# PROFIBUS_V4.net
KiCad netlist of a schematic drawn in EAGLE
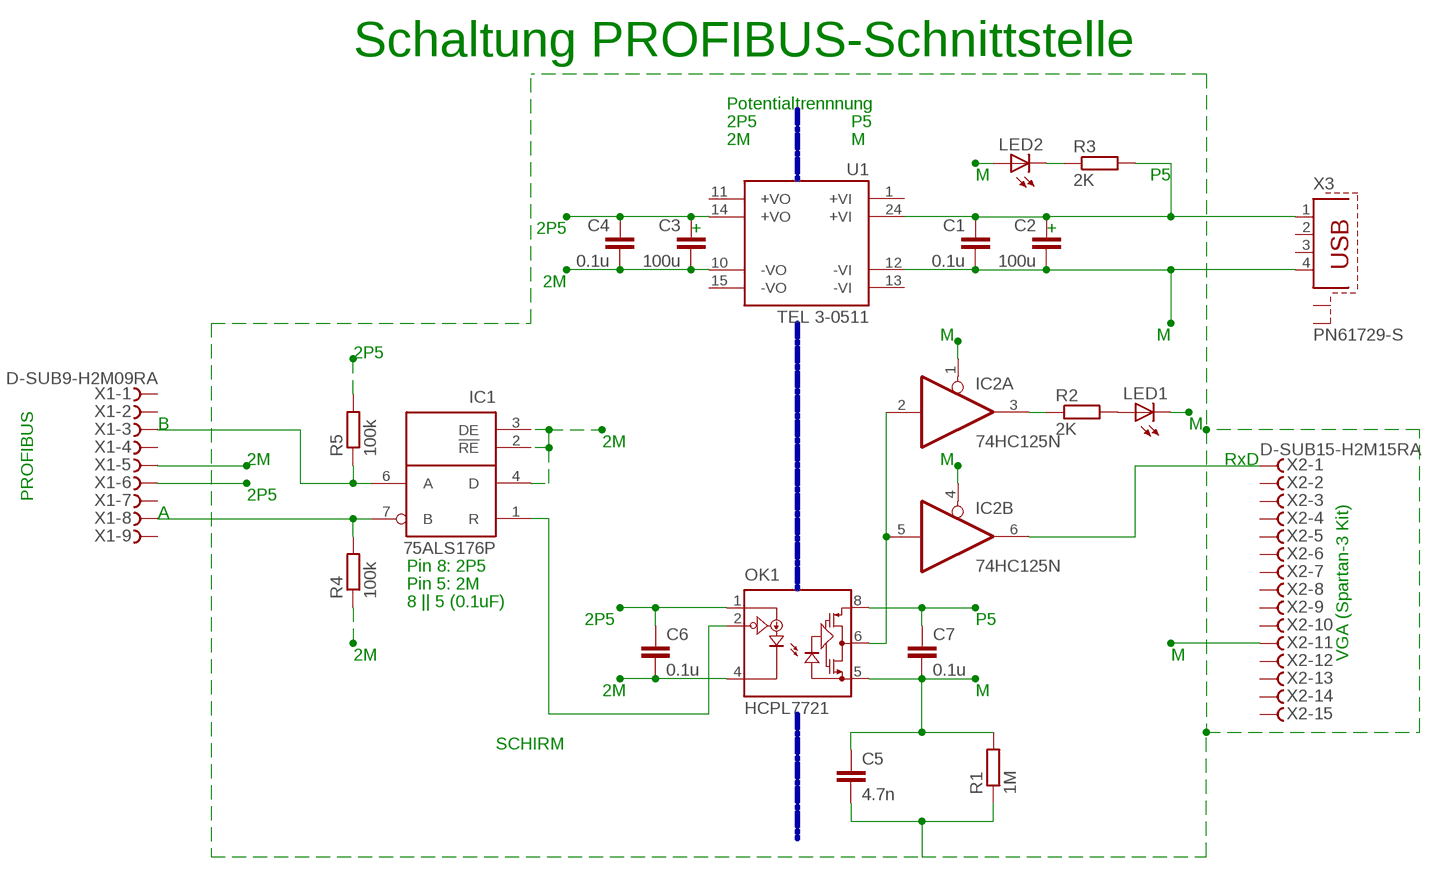
[diagram p0: schematic, sheet 1]

(export (version "E")
  (design (tool "Eeschema 10.0.6"))
  (components
    (comp (ref "C1")
      (value "0.1u")
      (footprint "eagle-import:C2.5-3")
      (libsource (lib "eagle-import") (part "C2,5-3"))
    )
    (comp (ref "C2")
      (value "100u")
      (footprint "eagle-import:C2.5-3")
      (libsource (lib "eagle-import") (part "C2,5-3"))
    )
    (comp (ref "C3")
      (value "100u")
      (footprint "eagle-import:C2.5-3")
      (libsource (lib "eagle-import") (part "C2,5-3"))
    )
    (comp (ref "C4")
      (value "0.1u")
      (footprint "eagle-import:C2.5-3")
      (libsource (lib "eagle-import") (part "C2,5-3"))
    )
    (comp (ref "C5")
      (value "4.7n")
      (footprint "eagle-import:C2.5-3")
      (libsource (lib "eagle-import") (part "C2,5-3"))
    )
    (comp (ref "C6")
      (value "0.1u")
      (footprint "eagle-import:C2.5-3")
      (libsource (lib "eagle-import") (part "C2,5-3"))
    )
    (comp (ref "C7")
      (value "0.1u")
      (footprint "eagle-import:C2.5-3")
      (libsource (lib "eagle-import") (part "C2,5-3"))
    )
    (comp (ref "IC1")
      (value "75ALS176P")
      (footprint "eagle-import:DIL08")
      (fields (field (name "MF") "TEXAS INSTRUMENTS") (field (name "MPN") "SN75ALS176P"))
      (libsource (lib "eagle-import") (part "75ALS176P"))
    )
    (comp (ref "IC2")
      (value "74HC125N")
      (footprint "eagle-import:DIL14")
      (libsource (lib "eagle-import") (part "74125NHC"))
    )
    (comp (ref "LED1")
      (value "TLLY4400")
      (footprint "eagle-import:LED3MM")
      (fields (field (name "MF") "VISHAY SEMICONDUCTOR"))
      (libsource (lib "eagle-import") (part "TLLY4400"))
    )
    (comp (ref "LED2")
      (value "TLLG4400")
      (footprint "eagle-import:LED3MM")
      (fields (field (name "MF") "VISHAY SEMICONDUCTOR"))
      (libsource (lib "eagle-import") (part "TLLG4400"))
    )
    (comp (ref "OK1")
      (value "HCPL7721")
      (footprint "eagle-import:DIL08")
      (fields (field (name "MF") "AGILENT TECHNOLOGIES") (field (name "MPN") "HCPL-7721"))
      (libsource (lib "eagle-import") (part "HCPL7721"))
    )
    (comp (ref "R1")
      (value "1M")
      (footprint "eagle-import:0204_7")
      (libsource (lib "eagle-import") (part "R-EU_0204/7"))
    )
    (comp (ref "R2")
      (value "2K")
      (footprint "eagle-import:0204_7")
      (libsource (lib "eagle-import") (part "R-EU_0204/7"))
    )
    (comp (ref "R3")
      (value "2K")
      (footprint "eagle-import:0204_7")
      (libsource (lib "eagle-import") (part "R-EU_0204/7"))
    )
    (comp (ref "R4")
      (value "100k")
      (footprint "eagle-import:0204_7")
      (libsource (lib "eagle-import") (part "R-EU_0204/7"))
    )
    (comp (ref "R5")
      (value "100k")
      (footprint "eagle-import:0204_7")
      (libsource (lib "eagle-import") (part "R-EU_0204/7"))
    )
    (comp (ref "U1")
      (value "TEL 3-0511")
      (footprint "eagle-import:AM3N_DIL24")
      (libsource (lib "eagle-import") (part "AM3N-S0505"))
    )
    (comp (ref "X1")
      (value "D-SUB9-H2M09RA")
      (footprint "eagle-import:H2M09RA")
      (libsource (lib "eagle-import") (part "D-SUB9-H2M09RA"))
    )
    (comp (ref "X2")
      (value "D-SUB15-H2M15RA")
      (footprint "eagle-import:H2M15RA")
      (fields (field (name "MPN") "H2M15RA29B"))
      (libsource (lib "eagle-import") (part "D-SUB15-H2M15RA"))
    )
    (comp (ref "X3")
      (value "PN61729-S")
      (footprint "eagle-import:PN61729-S")
      (libsource (lib "eagle-import") (part "PN61729-S"))
    )
  )
  (nets
    (net (code "1") (name "/+VI") (class "Default")
      (node (ref "U1") (pin "1") (pinfunction "+VI_1") (pintype "power_in"))
    )
    (net (code "2") (name "/+VO") (class "Default")
      (node (ref "U1") (pin "11") (pinfunction "+VO_11") (pintype "power_in"))
    )
    (net (code "3") (name "/-VI") (class "Default")
      (node (ref "U1") (pin "13") (pinfunction "-VI_13") (pintype "power_in"))
    )
    (net (code "4") (name "/-VO") (class "Default")
      (node (ref "U1") (pin "15") (pinfunction "-VO_15") (pintype "power_in"))
    )
    (net (code "5") (name "Net-(C1-Pad1)") (class "Default")
      (node (ref "C1") (pin "1") (pinfunction "1_1") (pintype "passive"))
      (node (ref "C2") (pin "1") (pinfunction "1_1") (pintype "passive"))
      (node (ref "R3") (pin "2") (pinfunction "2_2") (pintype "passive"))
      (node (ref "U1") (pin "24") (pinfunction "+VI_24") (pintype "power_in"))
      (node (ref "X3") (pin "1") (pinfunction "1_1") (pintype "passive"))
    )
    (net (code "6") (name "Net-(C1-Pad2)") (class "Default")
      (node (ref "C1") (pin "2") (pinfunction "2_2") (pintype "passive"))
      (node (ref "C2") (pin "2") (pinfunction "2_2") (pintype "passive"))
      (node (ref "U1") (pin "12") (pinfunction "-VI_12") (pintype "power_in"))
      (node (ref "X3") (pin "4") (pinfunction "4_4") (pintype "passive"))
    )
    (net (code "7") (name "Net-(C3-Pad1)") (class "Default")
      (node (ref "C3") (pin "1") (pinfunction "1_1") (pintype "passive"))
      (node (ref "C4") (pin "1") (pinfunction "1_1") (pintype "passive"))
      (node (ref "U1") (pin "14") (pinfunction "+VO_14") (pintype "power_in"))
    )
    (net (code "8") (name "Net-(C3-Pad2)") (class "Default")
      (node (ref "C3") (pin "2") (pinfunction "2_2") (pintype "passive"))
      (node (ref "C4") (pin "2") (pinfunction "2_2") (pintype "passive"))
      (node (ref "U1") (pin "10") (pinfunction "-VO_10") (pintype "power_in"))
    )
    (net (code "9") (name "Net-(C5-Pad2)") (class "Default")
      (node (ref "C5") (pin "2") (pinfunction "2_2") (pintype "passive"))
      (node (ref "R1") (pin "1") (pinfunction "1_1") (pintype "passive"))
    )
    (net (code "10") (name "Net-(IC1A-A)") (class "Default")
      (node (ref "IC1") (pin "6") (pinfunction "A_6") (pintype "bidirectional"))
      (node (ref "R5") (pin "1") (pinfunction "1_1") (pintype "passive"))
      (node (ref "X1") (pin "3") (pinfunction "F_3") (pintype "passive"))
    )
    (net (code "11") (name "Net-(IC1A-B)") (class "Default")
      (node (ref "IC1") (pin "7") (pinfunction "B_7") (pintype "bidirectional"))
      (node (ref "R4") (pin "2") (pinfunction "2_2") (pintype "passive"))
      (node (ref "X1") (pin "8") (pinfunction "F_8") (pintype "passive"))
    )
    (net (code "12") (name "Net-(IC1A-D)") (class "Default")
      (node (ref "IC1") (pin "2") (pinfunction "~{RE}_2") (pintype "input"))
      (node (ref "IC1") (pin "3") (pinfunction "DE_3") (pintype "input"))
      (node (ref "IC1") (pin "4") (pinfunction "D_4") (pintype "input"))
    )
    (net (code "13") (name "Net-(IC1A-R)") (class "Default")
      (node (ref "IC1") (pin "1") (pinfunction "R_1") (pintype "output"))
      (node (ref "OK1") (pin "2") (pinfunction "VI_2") (pintype "input"))
    )
    (net (code "14") (name "Net-(IC2A-I)") (class "Default")
      (node (ref "IC2") (pin "2") (pinfunction "I_2") (pintype "input"))
      (node (ref "IC2") (pin "5") (pinfunction "I_5") (pintype "input"))
      (node (ref "OK1") (pin "6") (pinfunction "VO_6") (pintype "passive"))
    )
    (net (code "15") (name "Net-(IC2A-O)") (class "Default")
      (node (ref "IC2") (pin "3") (pinfunction "O_3") (pintype "tri_state"))
      (node (ref "R2") (pin "1") (pinfunction "1_1") (pintype "passive"))
    )
    (net (code "16") (name "Net-(IC2B-O)") (class "Default")
      (node (ref "IC2") (pin "6") (pinfunction "O_6") (pintype "tri_state"))
      (node (ref "X2") (pin "1") (pinfunction "F_1") (pintype "passive"))
    )
    (net (code "17") (name "Net-(LED1-PadA)") (class "Default")
      (node (ref "LED1") (pin "A") (pinfunction "A_A") (pintype "passive"))
      (node (ref "R2") (pin "2") (pinfunction "2_2") (pintype "passive"))
    )
    (net (code "18") (name "Net-(LED2-C)") (class "Default")
      (node (ref "LED2") (pin "K") (pinfunction "C_K") (pintype "passive"))
      (node (ref "R3") (pin "1") (pinfunction "1_1") (pintype "passive"))
    )
    (net (code "19") (name "Net-(OK1-GND1)") (class "Default")
      (node (ref "C6") (pin "2") (pinfunction "2_2") (pintype "passive"))
      (node (ref "OK1") (pin "4") (pinfunction "GND1_4") (pintype "passive"))
    )
    (net (code "20") (name "Net-(OK1-GND2)") (class "Default")
      (node (ref "C5") (pin "1") (pinfunction "1_1") (pintype "passive"))
      (node (ref "C7") (pin "2") (pinfunction "2_2") (pintype "passive"))
      (node (ref "OK1") (pin "5") (pinfunction "GND2_5") (pintype "passive"))
      (node (ref "R1") (pin "2") (pinfunction "2_2") (pintype "passive"))
    )
    (net (code "21") (name "Net-(OK1-VDD1)") (class "Default")
      (node (ref "C6") (pin "1") (pinfunction "1_1") (pintype "passive"))
      (node (ref "OK1") (pin "1") (pinfunction "VDD1_1") (pintype "passive"))
    )
    (net (code "22") (name "Net-(OK1-VDD2)") (class "Default")
      (node (ref "C7") (pin "1") (pinfunction "1_1") (pintype "passive"))
      (node (ref "OK1") (pin "8") (pinfunction "VDD2_8") (pintype "passive"))
    )
    (net (code "23") (name "unconnected-(IC2A-OE-Pad1)") (class "Default")
      (node (ref "IC2") (pin "1") (pinfunction "OE_1") (pintype "input"))
    )
    (net (code "24") (name "unconnected-(IC2B-OE-Pad4)") (class "Default")
      (node (ref "IC2") (pin "4") (pinfunction "OE_4") (pintype "input"))
    )
    (net (code "25") (name "unconnected-(LED1-C-PadK)") (class "Default")
      (node (ref "LED1") (pin "K") (pinfunction "C_K") (pintype "passive"))
    )
    (net (code "26") (name "unconnected-(LED2-PadA)") (class "Default")
      (node (ref "LED2") (pin "A") (pinfunction "A_A") (pintype "passive"))
    )
    (net (code "27") (name "unconnected-(R4-Pad1)") (class "Default")
      (node (ref "R4") (pin "1") (pinfunction "1_1") (pintype "passive"))
    )
    (net (code "28") (name "unconnected-(R5-Pad2)") (class "Default")
      (node (ref "R5") (pin "2") (pinfunction "2_2") (pintype "passive"))
    )
    (net (code "29") (name "unconnected-(X1A-F-Pad1)") (class "Default")
      (node (ref "X1") (pin "1") (pinfunction "F_1") (pintype "passive"))
    )
    (net (code "30") (name "unconnected-(X1B-F-Pad2)") (class "Default")
      (node (ref "X1") (pin "2") (pinfunction "F_2") (pintype "passive"))
    )
    (net (code "31") (name "unconnected-(X1D-F-Pad4)") (class "Default")
      (node (ref "X1") (pin "4") (pinfunction "F_4") (pintype "passive"))
    )
    (net (code "32") (name "unconnected-(X1E-F-Pad5)") (class "Default")
      (node (ref "X1") (pin "5") (pinfunction "F_5") (pintype "passive"))
    )
    (net (code "33") (name "unconnected-(X1F-F-Pad6)") (class "Default")
      (node (ref "X1") (pin "6") (pinfunction "F_6") (pintype "passive"))
    )
    (net (code "34") (name "unconnected-(X1G-F-Pad7)") (class "Default")
      (node (ref "X1") (pin "7") (pinfunction "F_7") (pintype "passive"))
    )
    (net (code "35") (name "unconnected-(X1I-F-Pad9)") (class "Default")
      (node (ref "X1") (pin "9") (pinfunction "F_9") (pintype "passive"))
    )
    (net (code "36") (name "unconnected-(X2B-F-Pad10)") (class "Default")
      (node (ref "X2") (pin "10") (pinfunction "F_10") (pintype "passive"))
    )
    (net (code "37") (name "unconnected-(X2C-F-Pad11)") (class "Default")
      (node (ref "X2") (pin "11") (pinfunction "F_11") (pintype "passive"))
    )
    (net (code "38") (name "unconnected-(X2D-F-Pad12)") (class "Default")
      (node (ref "X2") (pin "12") (pinfunction "F_12") (pintype "passive"))
    )
    (net (code "39") (name "unconnected-(X2E-F-Pad13)") (class "Default")
      (node (ref "X2") (pin "13") (pinfunction "F_13") (pintype "passive"))
    )
    (net (code "40") (name "unconnected-(X2F-F-Pad14)") (class "Default")
      (node (ref "X2") (pin "14") (pinfunction "F_14") (pintype "passive"))
    )
    (net (code "41") (name "unconnected-(X2G-F-Pad15)") (class "Default")
      (node (ref "X2") (pin "15") (pinfunction "F_15") (pintype "passive"))
    )
    (net (code "42") (name "unconnected-(X2H-F-Pad2)") (class "Default")
      (node (ref "X2") (pin "2") (pinfunction "F_2") (pintype "passive"))
    )
    (net (code "43") (name "unconnected-(X2I-F-Pad3)") (class "Default")
      (node (ref "X2") (pin "3") (pinfunction "F_3") (pintype "passive"))
    )
    (net (code "44") (name "unconnected-(X2J-F-Pad4)") (class "Default")
      (node (ref "X2") (pin "4") (pinfunction "F_4") (pintype "passive"))
    )
    (net (code "45") (name "unconnected-(X2K-F-Pad5)") (class "Default")
      (node (ref "X2") (pin "5") (pinfunction "F_5") (pintype "passive"))
    )
    (net (code "46") (name "unconnected-(X2L-F-Pad6)") (class "Default")
      (node (ref "X2") (pin "6") (pinfunction "F_6") (pintype "passive"))
    )
    (net (code "47") (name "unconnected-(X2M-F-Pad7)") (class "Default")
      (node (ref "X2") (pin "7") (pinfunction "F_7") (pintype "passive"))
    )
    (net (code "48") (name "unconnected-(X2N-F-Pad8)") (class "Default")
      (node (ref "X2") (pin "8") (pinfunction "F_8") (pintype "passive"))
    )
    (net (code "49") (name "unconnected-(X2O-F-Pad9)") (class "Default")
      (node (ref "X2") (pin "9") (pinfunction "F_9") (pintype "passive"))
    )
    (net (code "50") (name "unconnected-(X3-Pad2)") (class "Default")
      (node (ref "X3") (pin "2") (pinfunction "2_2") (pintype "passive"))
    )
    (net (code "51") (name "unconnected-(X3-Pad3)") (class "Default")
      (node (ref "X3") (pin "3") (pinfunction "3_3") (pintype "passive"))
    )
    (net (code "52") (name "unconnected-(X3-PadS1)") (class "Default")
      (node (ref "X3") (pin "S1") (pinfunction "S1_S1") (pintype "passive"))
    )
    (net (code "53") (name "unconnected-(X3-PadS2)") (class "Default")
      (node (ref "X3") (pin "S2") (pinfunction "S2_S2") (pintype "passive"))
    )
  )
)
